# SLIVE.net
KiCad netlist of a schematic drawn in Altium Designer
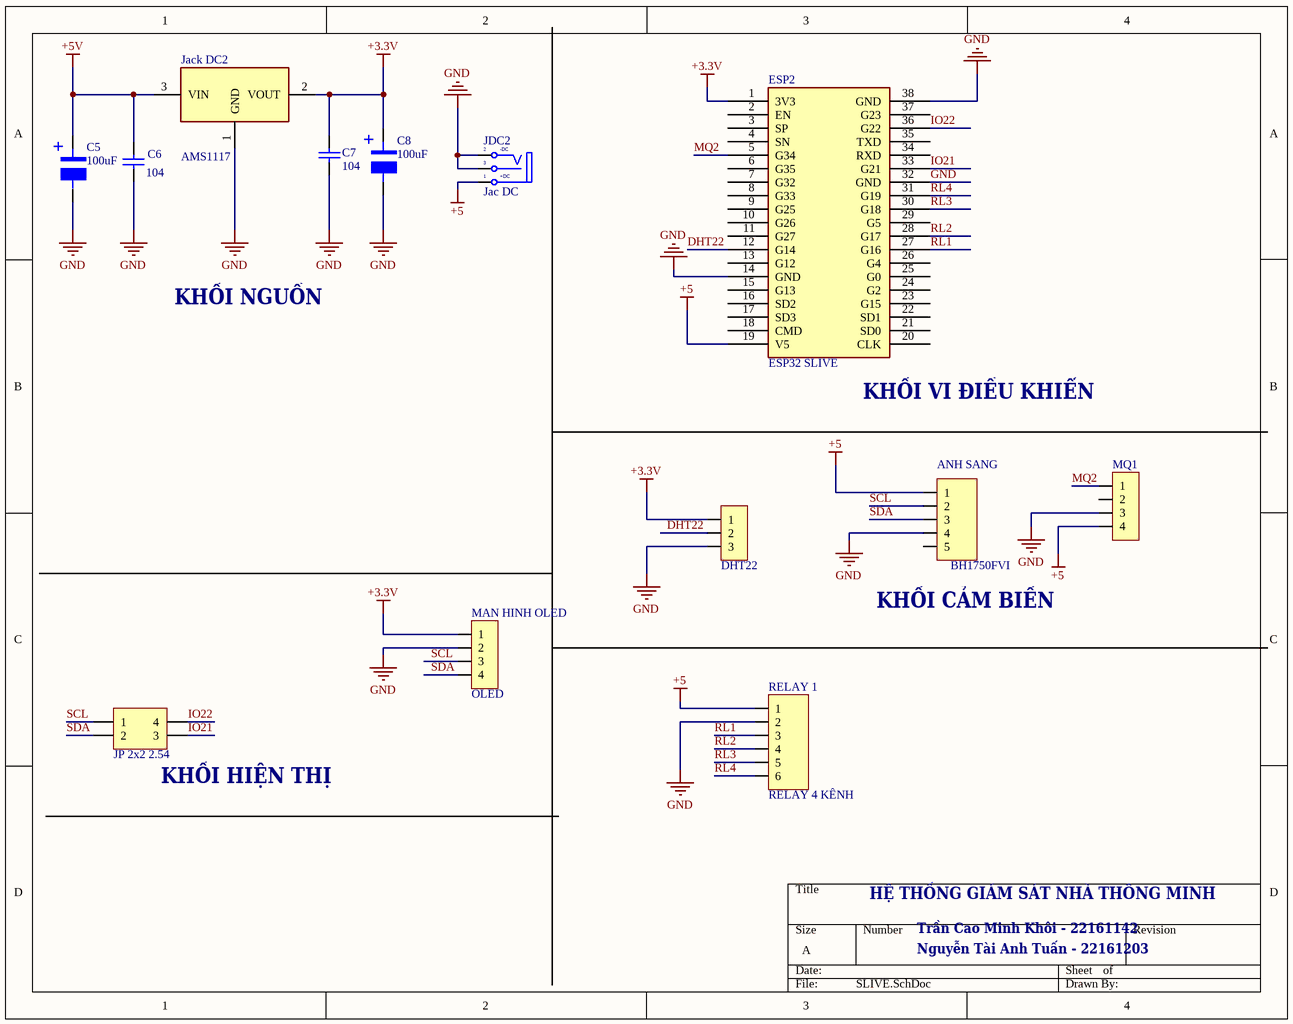
[diagram p0: SLIVE.SchDoc]

(export (version "E")
  (design (tool "Eeschema 10.0.6"))
  (components
    (comp (ref "ANH SANG")
      (value "BH1750FVI")
      (footprint "JP 1x5 DT")
      (description "Cắm")
      (libsource (lib "Altium_Lib_by_KhueNguyenCreator") (part "JP 1x5 2.54 Duc Thang"))
    )
    (comp (ref "C5")
      (value "100uF")
      (footprint "Cty1:100UF/16V_SMD")
      (libsource (lib "Cty1") (part "Cap100uF_SMD"))
    )
    (comp (ref "C6")
      (value "104")
      (footprint "tu 1206")
      (description "Dán")
      (libsource (lib "Altium_Lib_by_KhueNguyenCreator") (part "Tu 1206 104 50V 20%"))
    )
    (comp (ref "C7")
      (value "104")
      (footprint "tu 1206")
      (description "Dán")
      (libsource (lib "Altium_Lib_by_KhueNguyenCreator") (part "Tu 1206 104 50V 20%"))
    )
    (comp (ref "C8")
      (value "100uF")
      (footprint "Cty1:100UF/16V_SMD")
      (libsource (lib "Cty1") (part "Cap100uF_SMD"))
    )
    (comp (ref "DHT")
      (value "DHT22")
      (footprint "JP 1x3 CT")
      (description "Cắm")
      (libsource (lib "Altium_Lib_by_KhueNguyenCreator") (part "JP 1x3 2.54 Cai Thang"))
    )
    (comp (ref "ESP2")
      (value "ESP32 SLIVE")
      (footprint "ESP32_38")
      (description "Microcontoller Board 38 Pins Wifi 2.4GHz BLE 4.2 ESP32-WROOM-32D")
      (libsource (lib "Espressif Microcontrollers") (part "ESP32_38"))
    )
    (comp (ref "Jack DC2")
      (value "AMS1117")
      (footprint "AMS1117")
      (description "IC REG LINEAR 1A SOT-89-3L")
      (libsource (lib "Voltage Regulators") (part "AMS1117"))
    )
    (comp (ref "JDC2")
      (value "Jac DC")
      (footprint "DC-IN")
      (description "Jac DC input")
      (libsource (lib "Cty1") (part "DCIN"))
    )
    (comp (ref "JP1")
      (value "JP 2x2 2.54")
      (footprint "JP 2x2 DT")
      (description "Cắm")
      (libsource (lib "Altium_Lib_by_KhueNguyenCreator") (part "JP 2x2 2.54 Duc Thang"))
    )
    (comp (ref "MAN HINH OLED")
      (value "OLED")
      (footprint "JP 1x4 DT")
      (description "Cắm")
      (libsource (lib "Altium_Lib_by_KhueNguyenCreator") (part "JP 1x4 2.54 Duc Thang"))
    )
    (comp (ref "MQ1")
      (value "MQ2")
      (footprint "JP 1x4 CT")
      (description "Cắm")
      (libsource (lib "Altium_Lib_by_KhueNguyenCreator") (part "JP 1x4 2.54 Cai Thang"))
    )
    (comp (ref "RELAY 1")
      (value "RELAY 4 KÊNH")
      (footprint "JP 1x6 DC")
      (description "Cắm")
      (libsource (lib "Altium_Lib_by_KhueNguyenCreator") (part "JP 1x6 2.54 Duc Cong"))
    )
  )
  (nets
    (net (code "1") (name "+3.3V") (class "Default")
      (node (ref "C7") (pin "1") (pinfunction "1_1") (pintype "passive"))
      (node (ref "C8") (pin "1") (pinfunction "1_1") (pintype "passive"))
      (node (ref "DHT") (pin "1") (pinfunction "1_1") (pintype "passive"))
      (node (ref "ESP2") (pin "1") (pinfunction "3V3_1") (pintype "passive"))
      (node (ref "Jack DC2") (pin "2") (pinfunction "VOUT_2") (pintype "passive"))
      (node (ref "MAN HINH OLED") (pin "1") (pinfunction "1_1") (pintype "passive"))
    )
    (net (code "2") (name "+5") (class "Default")
      (node (ref "ANH SANG") (pin "1") (pinfunction "1_1") (pintype "passive"))
      (node (ref "ESP2") (pin "19") (pinfunction "V5_19") (pintype "passive"))
      (node (ref "JDC2") (pin "1") (pinfunction "T_1") (pintype "passive"))
      (node (ref "MQ1") (pin "4") (pinfunction "4_4") (pintype "passive"))
      (node (ref "RELAY 1") (pin "1") (pinfunction "1_1") (pintype "passive"))
    )
    (net (code "3") (name "+5V") (class "Default")
      (node (ref "C5") (pin "1") (pinfunction "1_1") (pintype "passive"))
      (node (ref "C6") (pin "1") (pinfunction "1_1") (pintype "passive"))
      (node (ref "Jack DC2") (pin "3") (pinfunction "VIN_3") (pintype "passive"))
    )
    (net (code "4") (name "/DHT22") (class "Default")
      (node (ref "DHT") (pin "2") (pinfunction "2_2") (pintype "passive"))
      (node (ref "ESP2") (pin "12") (pinfunction "G14_12") (pintype "passive"))
    )
    (net (code "5") (name "/IO21") (class "Default")
      (node (ref "ESP2") (pin "33") (pinfunction "G21_33") (pintype "passive"))
      (node (ref "JP1") (pin "3") (pinfunction "3_3") (pintype "passive"))
    )
    (net (code "6") (name "/IO22") (class "Default")
      (node (ref "ESP2") (pin "36") (pinfunction "G22_36") (pintype "passive"))
      (node (ref "JP1") (pin "4") (pinfunction "4_4") (pintype "passive"))
    )
    (net (code "7") (name "/MQ2") (class "Default")
      (node (ref "ESP2") (pin "5") (pinfunction "G34_5") (pintype "passive"))
      (node (ref "MQ1") (pin "1") (pinfunction "1_1") (pintype "passive"))
    )
    (net (code "8") (name "/RL1") (class "Default")
      (node (ref "ESP2") (pin "27") (pinfunction "G16_27") (pintype "passive"))
      (node (ref "RELAY 1") (pin "3") (pinfunction "3_3") (pintype "passive"))
    )
    (net (code "9") (name "/RL2") (class "Default")
      (node (ref "ESP2") (pin "28") (pinfunction "G17_28") (pintype "passive"))
      (node (ref "RELAY 1") (pin "4") (pinfunction "4_4") (pintype "passive"))
    )
    (net (code "10") (name "/RL3") (class "Default")
      (node (ref "ESP2") (pin "30") (pinfunction "G18_30") (pintype "passive"))
      (node (ref "RELAY 1") (pin "5") (pinfunction "5_5") (pintype "passive"))
    )
    (net (code "11") (name "/RL4") (class "Default")
      (node (ref "ESP2") (pin "31") (pinfunction "G19_31") (pintype "passive"))
      (node (ref "RELAY 1") (pin "6") (pinfunction "6_6") (pintype "passive"))
    )
    (net (code "12") (name "/SCL") (class "Default")
      (node (ref "ANH SANG") (pin "2") (pinfunction "2_2") (pintype "passive"))
      (node (ref "JP1") (pin "1") (pinfunction "1_1") (pintype "passive"))
      (node (ref "MAN HINH OLED") (pin "3") (pinfunction "3_3") (pintype "passive"))
    )
    (net (code "13") (name "/SDA") (class "Default")
      (node (ref "ANH SANG") (pin "3") (pinfunction "3_3") (pintype "passive"))
      (node (ref "JP1") (pin "2") (pinfunction "2_2") (pintype "passive"))
      (node (ref "MAN HINH OLED") (pin "4") (pinfunction "4_4") (pintype "passive"))
    )
    (net (code "14") (name "GND") (class "Default")
      (node (ref "ANH SANG") (pin "4") (pinfunction "4_4") (pintype "passive"))
      (node (ref "C5") (pin "2") (pinfunction "2_2") (pintype "passive"))
      (node (ref "C6") (pin "2") (pinfunction "2_2") (pintype "passive"))
      (node (ref "C7") (pin "2") (pinfunction "2_2") (pintype "passive"))
      (node (ref "C8") (pin "2") (pinfunction "2_2") (pintype "passive"))
      (node (ref "DHT") (pin "3") (pinfunction "3_3") (pintype "passive"))
      (node (ref "ESP2") (pin "14") (pinfunction "GND_14") (pintype "passive"))
      (node (ref "ESP2") (pin "32") (pinfunction "GND_32") (pintype "passive"))
      (node (ref "ESP2") (pin "38") (pinfunction "GND_38") (pintype "passive"))
      (node (ref "JDC2") (pin "2") (pinfunction "TN_2") (pintype "passive"))
      (node (ref "JDC2") (pin "3") (pinfunction "S_3") (pintype "power_in"))
      (node (ref "Jack DC2") (pin "1") (pinfunction "GND_1") (pintype "passive"))
      (node (ref "MAN HINH OLED") (pin "2") (pinfunction "2_2") (pintype "passive"))
      (node (ref "MQ1") (pin "3") (pinfunction "3_3") (pintype "passive"))
      (node (ref "RELAY 1") (pin "2") (pinfunction "2_2") (pintype "passive"))
    )
    (net (code "15") (name "unconnected-(ANH SANG-Pad5)") (class "Default")
      (node (ref "ANH SANG") (pin "5") (pinfunction "5_5") (pintype "passive"))
    )
    (net (code "16") (name "unconnected-(ESP2-CLK-Pad20)") (class "Default")
      (node (ref "ESP2") (pin "20") (pinfunction "CLK_20") (pintype "passive"))
    )
    (net (code "17") (name "unconnected-(ESP2-CMD-Pad18)") (class "Default")
      (node (ref "ESP2") (pin "18") (pinfunction "CMD_18") (pintype "passive"))
    )
    (net (code "18") (name "unconnected-(ESP2-EN-Pad2)") (class "Default")
      (node (ref "ESP2") (pin "2") (pinfunction "EN_2") (pintype "passive"))
    )
    (net (code "19") (name "unconnected-(ESP2-G0-Pad25)") (class "Default")
      (node (ref "ESP2") (pin "25") (pinfunction "G0_25") (pintype "passive"))
    )
    (net (code "20") (name "unconnected-(ESP2-G2-Pad24)") (class "Default")
      (node (ref "ESP2") (pin "24") (pinfunction "G2_24") (pintype "passive"))
    )
    (net (code "21") (name "unconnected-(ESP2-G4-Pad26)") (class "Default")
      (node (ref "ESP2") (pin "26") (pinfunction "G4_26") (pintype "passive"))
    )
    (net (code "22") (name "unconnected-(ESP2-G5-Pad29)") (class "Default")
      (node (ref "ESP2") (pin "29") (pinfunction "G5_29") (pintype "passive"))
    )
    (net (code "23") (name "unconnected-(ESP2-G12-Pad13)") (class "Default")
      (node (ref "ESP2") (pin "13") (pinfunction "G12_13") (pintype "passive"))
    )
    (net (code "24") (name "unconnected-(ESP2-G13-Pad15)") (class "Default")
      (node (ref "ESP2") (pin "15") (pinfunction "G13_15") (pintype "passive"))
    )
    (net (code "25") (name "unconnected-(ESP2-G15-Pad23)") (class "Default")
      (node (ref "ESP2") (pin "23") (pinfunction "G15_23") (pintype "passive"))
    )
    (net (code "26") (name "unconnected-(ESP2-G23-Pad37)") (class "Default")
      (node (ref "ESP2") (pin "37") (pinfunction "G23_37") (pintype "passive"))
    )
    (net (code "27") (name "unconnected-(ESP2-G25-Pad9)") (class "Default")
      (node (ref "ESP2") (pin "9") (pinfunction "G25_9") (pintype "passive"))
    )
    (net (code "28") (name "unconnected-(ESP2-G26-Pad10)") (class "Default")
      (node (ref "ESP2") (pin "10") (pinfunction "G26_10") (pintype "passive"))
    )
    (net (code "29") (name "unconnected-(ESP2-G27-Pad11)") (class "Default")
      (node (ref "ESP2") (pin "11") (pinfunction "G27_11") (pintype "passive"))
    )
    (net (code "30") (name "unconnected-(ESP2-G32-Pad7)") (class "Default")
      (node (ref "ESP2") (pin "7") (pinfunction "G32_7") (pintype "passive"))
    )
    (net (code "31") (name "unconnected-(ESP2-G33-Pad8)") (class "Default")
      (node (ref "ESP2") (pin "8") (pinfunction "G33_8") (pintype "passive"))
    )
    (net (code "32") (name "unconnected-(ESP2-G35-Pad6)") (class "Default")
      (node (ref "ESP2") (pin "6") (pinfunction "G35_6") (pintype "passive"))
    )
    (net (code "33") (name "unconnected-(ESP2-RXD-Pad34)") (class "Default")
      (node (ref "ESP2") (pin "34") (pinfunction "RXD_34") (pintype "passive"))
    )
    (net (code "34") (name "unconnected-(ESP2-SD0-Pad21)") (class "Default")
      (node (ref "ESP2") (pin "21") (pinfunction "SD0_21") (pintype "passive"))
    )
    (net (code "35") (name "unconnected-(ESP2-SD1-Pad22)") (class "Default")
      (node (ref "ESP2") (pin "22") (pinfunction "SD1_22") (pintype "passive"))
    )
    (net (code "36") (name "unconnected-(ESP2-SD2-Pad16)") (class "Default")
      (node (ref "ESP2") (pin "16") (pinfunction "SD2_16") (pintype "passive"))
    )
    (net (code "37") (name "unconnected-(ESP2-SD3-Pad17)") (class "Default")
      (node (ref "ESP2") (pin "17") (pinfunction "SD3_17") (pintype "passive"))
    )
    (net (code "38") (name "unconnected-(ESP2-SN-Pad4)") (class "Default")
      (node (ref "ESP2") (pin "4") (pinfunction "SN_4") (pintype "passive"))
    )
    (net (code "39") (name "unconnected-(ESP2-SP-Pad3)") (class "Default")
      (node (ref "ESP2") (pin "3") (pinfunction "SP_3") (pintype "passive"))
    )
    (net (code "40") (name "unconnected-(ESP2-TXD-Pad35)") (class "Default")
      (node (ref "ESP2") (pin "35") (pinfunction "TXD_35") (pintype "passive"))
    )
    (net (code "41") (name "unconnected-(MQ1-Pad2)") (class "Default")
      (node (ref "MQ1") (pin "2") (pinfunction "2_2") (pintype "passive"))
    )
  )
)
